# VoltageSensing.net
KiCad netlist of a schematic drawn in Altium Designer
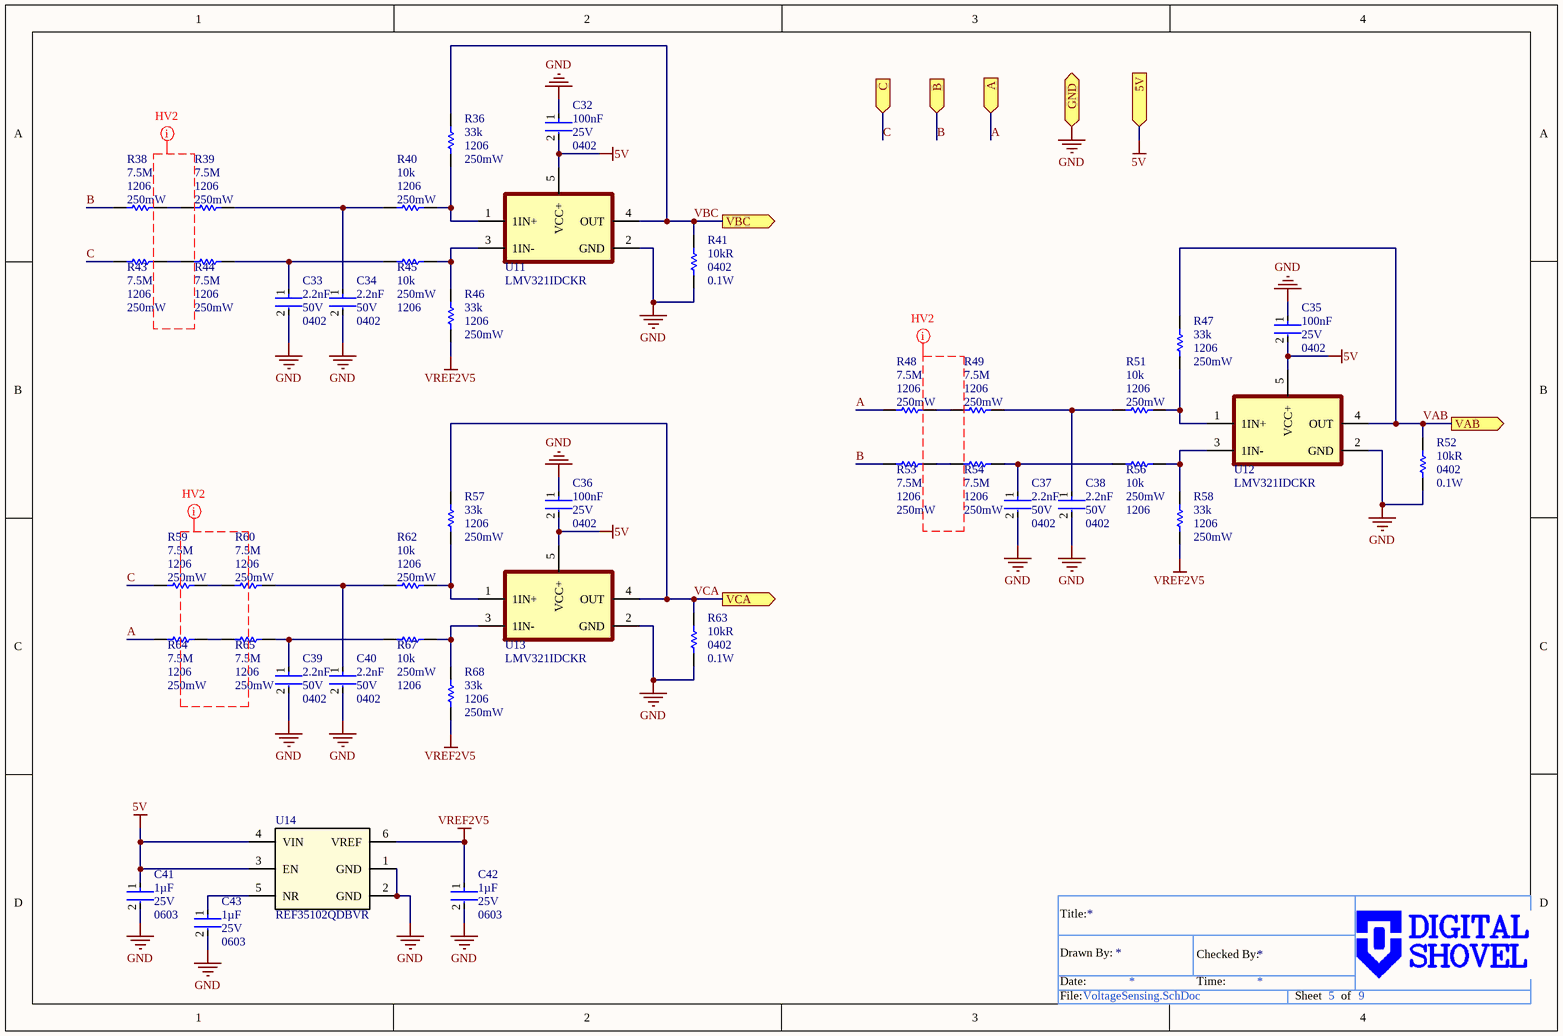
[diagram p0: VoltageSensing.SchDoc]

(export (version "E")
  (design (tool "Eeschema 10.0.6"))
  (components
    (comp (ref "C32")
      (value "100nF")
      (footprint "FP-CL830-IPC_A")
      (fields
        (field (name "VOLTAGE RATING") "25V")
        (field (name "CASE/PACKAGE") "0402")
        (field (name "Comment") "CL05B104KA5NNNC")
      )
      (libsource (lib "Digital Shovel") (part "b4654b650e69147ec39a6b967a45e02"))
    )
    (comp (ref "C33")
      (value "2.2nF")
      (footprint "FP-C0402-BB-IPC_A")
      (fields
        (field (name "VOLTAGE RATING") "50V")
        (field (name "CASE/PACKAGE") "0402")
        (field (name "Comment") "C0402C222J5RACTU")
      )
      (libsource (lib "Digital Shovel") (part "b4654b650e69147ec39a6b967a45e02"))
    )
    (comp (ref "C34")
      (value "2.2nF")
      (footprint "FP-C0402-BB-IPC_A")
      (fields
        (field (name "VOLTAGE RATING") "50V")
        (field (name "CASE/PACKAGE") "0402")
        (field (name "Comment") "C0402C222J5RACTU")
      )
      (libsource (lib "Digital Shovel") (part "b4654b650e69147ec39a6b967a45e02"))
    )
    (comp (ref "C35")
      (value "100nF")
      (footprint "FP-CL830-IPC_A")
      (fields
        (field (name "VOLTAGE RATING") "25V")
        (field (name "CASE/PACKAGE") "0402")
        (field (name "Comment") "CL05B104KA5NNNC")
      )
      (libsource (lib "Digital Shovel") (part "b4654b650e69147ec39a6b967a45e02"))
    )
    (comp (ref "C36")
      (value "100nF")
      (footprint "FP-CL830-IPC_A")
      (fields
        (field (name "VOLTAGE RATING") "25V")
        (field (name "CASE/PACKAGE") "0402")
        (field (name "Comment") "CL05B104KA5NNNC")
      )
      (libsource (lib "Digital Shovel") (part "b4654b650e69147ec39a6b967a45e02"))
    )
    (comp (ref "C37")
      (value "2.2nF")
      (footprint "FP-C0402-BB-IPC_A")
      (fields
        (field (name "VOLTAGE RATING") "50V")
        (field (name "CASE/PACKAGE") "0402")
        (field (name "Comment") "C0402C222J5RACTU")
      )
      (libsource (lib "Digital Shovel") (part "b4654b650e69147ec39a6b967a45e02"))
    )
    (comp (ref "C38")
      (value "2.2nF")
      (footprint "FP-C0402-BB-IPC_A")
      (fields
        (field (name "VOLTAGE RATING") "50V")
        (field (name "CASE/PACKAGE") "0402")
        (field (name "Comment") "C0402C222J5RACTU")
      )
      (libsource (lib "Digital Shovel") (part "b4654b650e69147ec39a6b967a45e02"))
    )
    (comp (ref "C39")
      (value "2.2nF")
      (footprint "FP-C0402-BB-IPC_A")
      (fields
        (field (name "VOLTAGE RATING") "50V")
        (field (name "CASE/PACKAGE") "0402")
        (field (name "Comment") "C0402C222J5RACTU")
      )
      (libsource (lib "Digital Shovel") (part "b4654b650e69147ec39a6b967a45e02"))
    )
    (comp (ref "C40")
      (value "2.2nF")
      (footprint "FP-C0402-BB-IPC_A")
      (fields
        (field (name "VOLTAGE RATING") "50V")
        (field (name "CASE/PACKAGE") "0402")
        (field (name "Comment") "C0402C222J5RACTU")
      )
      (libsource (lib "Digital Shovel") (part "b4654b650e69147ec39a6b967a45e02"))
    )
    (comp (ref "C41")
      (value "1µF")
      (footprint "FP-0603-L_1_6_0_1-W_0_8_0-IPC_A")
      (fields
        (field (name "VOLTAGE RATING") "25V")
        (field (name "CASE/PACKAGE") "0603")
        (field (name "Comment") "TMK107B7105KA-T")
      )
      (libsource (lib "Digital Shovel") (part "02cd4be3c70576c341d710602a673aa"))
    )
    (comp (ref "C42")
      (value "1µF")
      (footprint "FP-0603-L_1_6_0_1-W_0_8_0-IPC_A")
      (fields
        (field (name "VOLTAGE RATING") "25V")
        (field (name "CASE/PACKAGE") "0603")
        (field (name "Comment") "TMK107B7105KA-T")
      )
      (libsource (lib "Digital Shovel") (part "02cd4be3c70576c341d710602a673aa"))
    )
    (comp (ref "C43")
      (value "1µF")
      (footprint "FP-0603-L_1_6_0_1-W_0_8_0-IPC_A")
      (fields
        (field (name "VOLTAGE RATING") "25V")
        (field (name "CASE/PACKAGE") "0603")
        (field (name "Comment") "TMK107B7105KA-T")
      )
      (libsource (lib "Digital Shovel") (part "02cd4be3c70576c341d710602a673aa"))
    )
    (comp (ref "R36")
      (value "33k")
      (footprint "RESC3216X70X40NL20T20")
      (fields
        (field (name "POWER") "250mW")
        (field (name "TOLERANCE") "1%")
        (field (name "CASE/PACKAGE") "1206")
        (field (name "Comment") "RK73H2BTTD3302F")
      )
      (libsource (lib "Digital Shovel") (part "RES"))
    )
    (comp (ref "R38")
      (value "7.5M")
      (footprint "FP-KTR18-IPC_A")
      (description "Fixed Resistor, 0.25W, 7500000ohm, 500V, 1% +/-Tol, 100ppm/Cel, Surface Mount, 1206")
      (fields
        (field (name "CASE/PACKAGE") "1206")
        (field (name "POWER") "250mW")
        (field (name "TOLERANCE") "1%")
        (field (name "Comment") "KTR18EZPF7504")
      )
      (libsource (lib "Digital Shovel") (part "RES"))
    )
    (comp (ref "R39")
      (value "7.5M")
      (footprint "FP-KTR18-IPC_A")
      (description "Fixed Resistor, 0.25W, 7500000ohm, 500V, 1% +/-Tol, 100ppm/Cel, Surface Mount, 1206")
      (fields
        (field (name "CASE/PACKAGE") "1206")
        (field (name "POWER") "250mW")
        (field (name "TOLERANCE") "1%")
        (field (name "Comment") "KTR18EZPF7504")
      )
      (libsource (lib "Digital Shovel") (part "RES"))
    )
    (comp (ref "R40")
      (value "10k")
      (footprint "RESC3216X70X40NL20T20")
      (fields
        (field (name "POWER") "250mW")
        (field (name "CASE/PACKAGE") "1206")
        (field (name "TOLERANCE") "1%")
        (field (name "Comment") "RK73H2BTTD1002F")
      )
      (libsource (lib "Digital Shovel") (part "RES"))
    )
    (comp (ref "R41")
      (value "10kR")
      (footprint "RESC1005X40X25LL10T10")
      (fields
        (field (name "PACKAGE") "0402")
        (field (name "POWER") "0.1W")
        (field (name "Comment") "RK73H1ETTP1002F")
      )
      (libsource (lib "Digital Shovel") (part "RES"))
    )
    (comp (ref "R43")
      (value "7.5M")
      (footprint "FP-KTR18-IPC_A")
      (description "Fixed Resistor, 0.25W, 7500000ohm, 500V, 1% +/-Tol, 100ppm/Cel, Surface Mount, 1206")
      (fields
        (field (name "CASE/PACKAGE") "1206")
        (field (name "POWER") "250mW")
        (field (name "TOLERANCE") "1%")
        (field (name "Comment") "KTR18EZPF7504")
      )
      (libsource (lib "Digital Shovel") (part "RES"))
    )
    (comp (ref "R44")
      (value "7.5M")
      (footprint "FP-KTR18-IPC_A")
      (description "Fixed Resistor, 0.25W, 7500000ohm, 500V, 1% +/-Tol, 100ppm/Cel, Surface Mount, 1206")
      (fields
        (field (name "CASE/PACKAGE") "1206")
        (field (name "POWER") "250mW")
        (field (name "TOLERANCE") "1%")
        (field (name "Comment") "KTR18EZPF7504")
      )
      (libsource (lib "Digital Shovel") (part "RES"))
    )
    (comp (ref "R45")
      (value "10k")
      (footprint "RESC3216X70X40NL20T20")
      (fields
        (field (name "POWER") "250mW")
        (field (name "CASE/PACKAGE") "1206")
        (field (name "TOLERANCE") "1%")
        (field (name "Comment") "RK73H2BTTD1002F")
      )
      (libsource (lib "Digital Shovel") (part "RES"))
    )
    (comp (ref "R46")
      (value "33k")
      (footprint "RESC3216X70X40NL20T20")
      (fields
        (field (name "POWER") "250mW")
        (field (name "TOLERANCE") "1%")
        (field (name "CASE/PACKAGE") "1206")
        (field (name "Comment") "RK73H2BTTD3302F")
      )
      (libsource (lib "Digital Shovel") (part "RES"))
    )
    (comp (ref "R47")
      (value "33k")
      (footprint "RESC3216X70X40NL20T20")
      (fields
        (field (name "POWER") "250mW")
        (field (name "TOLERANCE") "1%")
        (field (name "CASE/PACKAGE") "1206")
        (field (name "Comment") "RK73H2BTTD3302F")
      )
      (libsource (lib "Digital Shovel") (part "RES"))
    )
    (comp (ref "R48")
      (value "7.5M")
      (footprint "FP-KTR18-IPC_A")
      (description "Fixed Resistor, 0.25W, 7500000ohm, 500V, 1% +/-Tol, 100ppm/Cel, Surface Mount, 1206")
      (fields
        (field (name "CASE/PACKAGE") "1206")
        (field (name "POWER") "250mW")
        (field (name "TOLERANCE") "1%")
        (field (name "Comment") "KTR18EZPF7504")
      )
      (libsource (lib "Digital Shovel") (part "RES"))
    )
    (comp (ref "R49")
      (value "7.5M")
      (footprint "FP-KTR18-IPC_A")
      (description "Fixed Resistor, 0.25W, 7500000ohm, 500V, 1% +/-Tol, 100ppm/Cel, Surface Mount, 1206")
      (fields
        (field (name "CASE/PACKAGE") "1206")
        (field (name "POWER") "250mW")
        (field (name "TOLERANCE") "1%")
        (field (name "Comment") "KTR18EZPF7504")
      )
      (libsource (lib "Digital Shovel") (part "RES"))
    )
    (comp (ref "R51")
      (value "10k")
      (footprint "RESC3216X70X40NL20T20")
      (fields
        (field (name "POWER") "250mW")
        (field (name "CASE/PACKAGE") "1206")
        (field (name "TOLERANCE") "1%")
        (field (name "Comment") "RK73H2BTTD1002F")
      )
      (libsource (lib "Digital Shovel") (part "RES"))
    )
    (comp (ref "R52")
      (value "10kR")
      (footprint "RESC1005X40X25LL10T10")
      (fields
        (field (name "PACKAGE") "0402")
        (field (name "POWER") "0.1W")
        (field (name "Comment") "RK73H1ETTP1002F")
      )
      (libsource (lib "Digital Shovel") (part "RES"))
    )
    (comp (ref "R53")
      (value "7.5M")
      (footprint "FP-KTR18-IPC_A")
      (description "Fixed Resistor, 0.25W, 7500000ohm, 500V, 1% +/-Tol, 100ppm/Cel, Surface Mount, 1206")
      (fields
        (field (name "CASE/PACKAGE") "1206")
        (field (name "POWER") "250mW")
        (field (name "TOLERANCE") "1%")
        (field (name "Comment") "KTR18EZPF7504")
      )
      (libsource (lib "Digital Shovel") (part "RES"))
    )
    (comp (ref "R54")
      (value "7.5M")
      (footprint "FP-KTR18-IPC_A")
      (description "Fixed Resistor, 0.25W, 7500000ohm, 500V, 1% +/-Tol, 100ppm/Cel, Surface Mount, 1206")
      (fields
        (field (name "CASE/PACKAGE") "1206")
        (field (name "POWER") "250mW")
        (field (name "TOLERANCE") "1%")
        (field (name "Comment") "KTR18EZPF7504")
      )
      (libsource (lib "Digital Shovel") (part "RES"))
    )
    (comp (ref "R56")
      (value "10k")
      (footprint "RESC3216X70X40NL20T20")
      (fields
        (field (name "POWER") "250mW")
        (field (name "CASE/PACKAGE") "1206")
        (field (name "TOLERANCE") "1%")
        (field (name "Comment") "RK73H2BTTD1002F")
      )
      (libsource (lib "Digital Shovel") (part "RES"))
    )
    (comp (ref "R57")
      (value "33k")
      (footprint "RESC3216X70X40NL20T20")
      (fields
        (field (name "POWER") "250mW")
        (field (name "TOLERANCE") "1%")
        (field (name "CASE/PACKAGE") "1206")
        (field (name "Comment") "RK73H2BTTD3302F")
      )
      (libsource (lib "Digital Shovel") (part "RES"))
    )
    (comp (ref "R58")
      (value "33k")
      (footprint "RESC3216X70X40NL20T20")
      (fields
        (field (name "POWER") "250mW")
        (field (name "TOLERANCE") "1%")
        (field (name "CASE/PACKAGE") "1206")
        (field (name "Comment") "RK73H2BTTD3302F")
      )
      (libsource (lib "Digital Shovel") (part "RES"))
    )
    (comp (ref "R59")
      (value "7.5M")
      (footprint "FP-KTR18-IPC_A")
      (description "Fixed Resistor, 0.25W, 7500000ohm, 500V, 1% +/-Tol, 100ppm/Cel, Surface Mount, 1206")
      (fields
        (field (name "CASE/PACKAGE") "1206")
        (field (name "POWER") "250mW")
        (field (name "TOLERANCE") "1%")
        (field (name "Comment") "KTR18EZPF7504")
      )
      (libsource (lib "Digital Shovel") (part "RES"))
    )
    (comp (ref "R60")
      (value "7.5M")
      (footprint "FP-KTR18-IPC_A")
      (description "Fixed Resistor, 0.25W, 7500000ohm, 500V, 1% +/-Tol, 100ppm/Cel, Surface Mount, 1206")
      (fields
        (field (name "CASE/PACKAGE") "1206")
        (field (name "POWER") "250mW")
        (field (name "TOLERANCE") "1%")
        (field (name "Comment") "KTR18EZPF7504")
      )
      (libsource (lib "Digital Shovel") (part "RES"))
    )
    (comp (ref "R62")
      (value "10k")
      (footprint "RESC3216X70X40NL20T20")
      (fields
        (field (name "POWER") "250mW")
        (field (name "CASE/PACKAGE") "1206")
        (field (name "TOLERANCE") "1%")
        (field (name "Comment") "RK73H2BTTD1002F")
      )
      (libsource (lib "Digital Shovel") (part "RES"))
    )
    (comp (ref "R63")
      (value "10kR")
      (footprint "RESC1005X40X25LL10T10")
      (fields
        (field (name "PACKAGE") "0402")
        (field (name "POWER") "0.1W")
        (field (name "Comment") "RK73H1ETTP1002F")
      )
      (libsource (lib "Digital Shovel") (part "RES"))
    )
    (comp (ref "R64")
      (value "7.5M")
      (footprint "FP-KTR18-IPC_A")
      (description "Fixed Resistor, 0.25W, 7500000ohm, 500V, 1% +/-Tol, 100ppm/Cel, Surface Mount, 1206")
      (fields
        (field (name "CASE/PACKAGE") "1206")
        (field (name "POWER") "250mW")
        (field (name "TOLERANCE") "1%")
        (field (name "Comment") "KTR18EZPF7504")
      )
      (libsource (lib "Digital Shovel") (part "RES"))
    )
    (comp (ref "R65")
      (value "7.5M")
      (footprint "FP-KTR18-IPC_A")
      (description "Fixed Resistor, 0.25W, 7500000ohm, 500V, 1% +/-Tol, 100ppm/Cel, Surface Mount, 1206")
      (fields
        (field (name "CASE/PACKAGE") "1206")
        (field (name "POWER") "250mW")
        (field (name "TOLERANCE") "1%")
        (field (name "Comment") "KTR18EZPF7504")
      )
      (libsource (lib "Digital Shovel") (part "RES"))
    )
    (comp (ref "R67")
      (value "10k")
      (footprint "RESC3216X70X40NL20T20")
      (fields
        (field (name "POWER") "250mW")
        (field (name "CASE/PACKAGE") "1206")
        (field (name "TOLERANCE") "1%")
        (field (name "Comment") "RK73H2BTTD1002F")
      )
      (libsource (lib "Digital Shovel") (part "RES"))
    )
    (comp (ref "R68")
      (value "33k")
      (footprint "RESC3216X70X40NL20T20")
      (fields
        (field (name "POWER") "250mW")
        (field (name "TOLERANCE") "1%")
        (field (name "CASE/PACKAGE") "1206")
        (field (name "Comment") "RK73H2BTTD3302F")
      )
      (libsource (lib "Digital Shovel") (part "RES"))
    )
    (comp (ref "U11")
      (value "LMV321IDCKR")
      (footprint "LMV321IDCKR-Footprint-1")
      (description "Operational Amplifier, 1 Func, 7000uV Offset-Max, BIPolar, PDSO5")
      (libsource (lib "Digital Shovel") (part "TLV9104QPWRQ1"))
    )
    (comp (ref "U12")
      (value "LMV321IDCKR")
      (footprint "LMV321IDCKR-Footprint-1")
      (description "Operational Amplifier, 1 Func, 7000uV Offset-Max, BIPolar, PDSO5")
      (libsource (lib "Digital Shovel") (part "TLV9104QPWRQ1"))
    )
    (comp (ref "U13")
      (value "LMV321IDCKR")
      (footprint "LMV321IDCKR-Footprint-1")
      (description "Operational Amplifier, 1 Func, 7000uV Offset-Max, BIPolar, PDSO5")
      (libsource (lib "Digital Shovel") (part "TLV9104QPWRQ1"))
    )
    (comp (ref "U14")
      (value "REF35102QDBVR")
      (footprint "REF35102QDBVR-Footprint-1")
      (libsource (lib "Digital Shovel") (part "REF35102QDBVR"))
    )
  )
  (nets
    (net (code "1") (name "/A") (class "Default")
      (node (ref "R48") (pin "2") (pinfunction "2_2") (pintype "passive"))
      (node (ref "R64") (pin "2") (pinfunction "2_2") (pintype "passive"))
    )
    (net (code "2") (name "/B") (class "Default")
      (node (ref "R38") (pin "2") (pinfunction "2_2") (pintype "passive"))
      (node (ref "R53") (pin "2") (pinfunction "2_2") (pintype "passive"))
    )
    (net (code "3") (name "/C") (class "Default")
      (node (ref "R43") (pin "2") (pinfunction "2_2") (pintype "passive"))
      (node (ref "R59") (pin "2") (pinfunction "2_2") (pintype "passive"))
    )
    (net (code "4") (name "/VAB") (class "Default")
      (node (ref "R47") (pin "2") (pinfunction "2_2") (pintype "passive"))
      (node (ref "R52") (pin "1") (pinfunction "1_1") (pintype "passive"))
      (node (ref "U12") (pin "4") (pinfunction "OUT_4") (pintype "passive"))
    )
    (net (code "5") (name "/VBC") (class "Default")
      (node (ref "R36") (pin "2") (pinfunction "2_2") (pintype "passive"))
      (node (ref "R41") (pin "1") (pinfunction "1_1") (pintype "passive"))
      (node (ref "U11") (pin "4") (pinfunction "OUT_4") (pintype "passive"))
    )
    (net (code "6") (name "/VCA") (class "Default")
      (node (ref "R57") (pin "2") (pinfunction "2_2") (pintype "passive"))
      (node (ref "R63") (pin "1") (pinfunction "1_1") (pintype "passive"))
      (node (ref "U13") (pin "4") (pinfunction "OUT_4") (pintype "passive"))
    )
    (net (code "7") (name "5V") (class "Default")
      (node (ref "C32") (pin "2") (pinfunction "2_2") (pintype "passive"))
      (node (ref "C35") (pin "2") (pinfunction "2_2") (pintype "passive"))
      (node (ref "C36") (pin "2") (pinfunction "2_2") (pintype "passive"))
      (node (ref "C41") (pin "1") (pinfunction "1_1") (pintype "passive"))
      (node (ref "U11") (pin "5") (pinfunction "VCC+_5") (pintype "passive"))
      (node (ref "U12") (pin "5") (pinfunction "VCC+_5") (pintype "passive"))
      (node (ref "U13") (pin "5") (pinfunction "VCC+_5") (pintype "passive"))
      (node (ref "U14") (pin "3") (pinfunction "EN_3") (pintype "passive"))
      (node (ref "U14") (pin "4") (pinfunction "VIN_4") (pintype "passive"))
    )
    (net (code "8") (name "GND") (class "Default")
      (node (ref "C32") (pin "1") (pinfunction "1_1") (pintype "passive"))
      (node (ref "C33") (pin "2") (pinfunction "2_2") (pintype "passive"))
      (node (ref "C34") (pin "2") (pinfunction "2_2") (pintype "passive"))
      (node (ref "C35") (pin "1") (pinfunction "1_1") (pintype "passive"))
      (node (ref "C36") (pin "1") (pinfunction "1_1") (pintype "passive"))
      (node (ref "C37") (pin "2") (pinfunction "2_2") (pintype "passive"))
      (node (ref "C38") (pin "2") (pinfunction "2_2") (pintype "passive"))
      (node (ref "C39") (pin "2") (pinfunction "2_2") (pintype "passive"))
      (node (ref "C40") (pin "2") (pinfunction "2_2") (pintype "passive"))
      (node (ref "C41") (pin "2") (pinfunction "2_2") (pintype "passive"))
      (node (ref "C42") (pin "2") (pinfunction "2_2") (pintype "passive"))
      (node (ref "C43") (pin "2") (pinfunction "2_2") (pintype "passive"))
      (node (ref "R41") (pin "2") (pinfunction "2_2") (pintype "passive"))
      (node (ref "R52") (pin "2") (pinfunction "2_2") (pintype "passive"))
      (node (ref "R63") (pin "2") (pinfunction "2_2") (pintype "passive"))
      (node (ref "U11") (pin "2") (pinfunction "GND_2") (pintype "passive"))
      (node (ref "U12") (pin "2") (pinfunction "GND_2") (pintype "passive"))
      (node (ref "U13") (pin "2") (pinfunction "GND_2") (pintype "passive"))
      (node (ref "U14") (pin "1") (pinfunction "GND_1") (pintype "passive"))
      (node (ref "U14") (pin "2") (pinfunction "GND_2") (pintype "passive"))
    )
    (net (code "9") (name "Net-(C33-Pad1)") (class "Default")
      (node (ref "C33") (pin "1") (pinfunction "1_1") (pintype "passive"))
      (node (ref "R44") (pin "1") (pinfunction "1_1") (pintype "passive"))
      (node (ref "R45") (pin "1") (pinfunction "1_1") (pintype "passive"))
    )
    (net (code "10") (name "Net-(C34-Pad1)") (class "Default")
      (node (ref "C34") (pin "1") (pinfunction "1_1") (pintype "passive"))
      (node (ref "R39") (pin "1") (pinfunction "1_1") (pintype "passive"))
      (node (ref "R40") (pin "1") (pinfunction "1_1") (pintype "passive"))
    )
    (net (code "11") (name "Net-(C37-Pad1)") (class "Default")
      (node (ref "C37") (pin "1") (pinfunction "1_1") (pintype "passive"))
      (node (ref "R54") (pin "1") (pinfunction "1_1") (pintype "passive"))
      (node (ref "R56") (pin "1") (pinfunction "1_1") (pintype "passive"))
    )
    (net (code "12") (name "Net-(C38-Pad1)") (class "Default")
      (node (ref "C38") (pin "1") (pinfunction "1_1") (pintype "passive"))
      (node (ref "R49") (pin "1") (pinfunction "1_1") (pintype "passive"))
      (node (ref "R51") (pin "1") (pinfunction "1_1") (pintype "passive"))
    )
    (net (code "13") (name "Net-(C39-Pad1)") (class "Default")
      (node (ref "C39") (pin "1") (pinfunction "1_1") (pintype "passive"))
      (node (ref "R65") (pin "1") (pinfunction "1_1") (pintype "passive"))
      (node (ref "R67") (pin "1") (pinfunction "1_1") (pintype "passive"))
    )
    (net (code "14") (name "Net-(C40-Pad1)") (class "Default")
      (node (ref "C40") (pin "1") (pinfunction "1_1") (pintype "passive"))
      (node (ref "R60") (pin "1") (pinfunction "1_1") (pintype "passive"))
      (node (ref "R62") (pin "1") (pinfunction "1_1") (pintype "passive"))
    )
    (net (code "15") (name "Net-(R38-Pad1)") (class "Default")
      (node (ref "R38") (pin "1") (pinfunction "1_1") (pintype "passive"))
      (node (ref "R39") (pin "2") (pinfunction "2_2") (pintype "passive"))
    )
    (net (code "16") (name "Net-(R43-Pad1)") (class "Default")
      (node (ref "R43") (pin "1") (pinfunction "1_1") (pintype "passive"))
      (node (ref "R44") (pin "2") (pinfunction "2_2") (pintype "passive"))
    )
    (net (code "17") (name "Net-(R48-Pad1)") (class "Default")
      (node (ref "R48") (pin "1") (pinfunction "1_1") (pintype "passive"))
      (node (ref "R49") (pin "2") (pinfunction "2_2") (pintype "passive"))
    )
    (net (code "18") (name "Net-(R53-Pad1)") (class "Default")
      (node (ref "R53") (pin "1") (pinfunction "1_1") (pintype "passive"))
      (node (ref "R54") (pin "2") (pinfunction "2_2") (pintype "passive"))
    )
    (net (code "19") (name "Net-(R59-Pad1)") (class "Default")
      (node (ref "R59") (pin "1") (pinfunction "1_1") (pintype "passive"))
      (node (ref "R60") (pin "2") (pinfunction "2_2") (pintype "passive"))
    )
    (net (code "20") (name "Net-(R64-Pad1)") (class "Default")
      (node (ref "R64") (pin "1") (pinfunction "1_1") (pintype "passive"))
      (node (ref "R65") (pin "2") (pinfunction "2_2") (pintype "passive"))
    )
    (net (code "21") (name "Net-(U11-1IN+)") (class "Default")
      (node (ref "R36") (pin "1") (pinfunction "1_1") (pintype "passive"))
      (node (ref "R40") (pin "2") (pinfunction "2_2") (pintype "passive"))
      (node (ref "U11") (pin "1") (pinfunction "1IN+_1") (pintype "passive"))
    )
    (net (code "22") (name "Net-(U11-1IN-)") (class "Default")
      (node (ref "R45") (pin "2") (pinfunction "2_2") (pintype "passive"))
      (node (ref "R46") (pin "2") (pinfunction "2_2") (pintype "passive"))
      (node (ref "U11") (pin "3") (pinfunction "1IN-_3") (pintype "passive"))
    )
    (net (code "23") (name "Net-(U12-1IN+)") (class "Default")
      (node (ref "R47") (pin "1") (pinfunction "1_1") (pintype "passive"))
      (node (ref "R51") (pin "2") (pinfunction "2_2") (pintype "passive"))
      (node (ref "U12") (pin "1") (pinfunction "1IN+_1") (pintype "passive"))
    )
    (net (code "24") (name "Net-(U12-1IN-)") (class "Default")
      (node (ref "R56") (pin "2") (pinfunction "2_2") (pintype "passive"))
      (node (ref "R58") (pin "2") (pinfunction "2_2") (pintype "passive"))
      (node (ref "U12") (pin "3") (pinfunction "1IN-_3") (pintype "passive"))
    )
    (net (code "25") (name "Net-(U13-1IN+)") (class "Default")
      (node (ref "R57") (pin "1") (pinfunction "1_1") (pintype "passive"))
      (node (ref "R62") (pin "2") (pinfunction "2_2") (pintype "passive"))
      (node (ref "U13") (pin "1") (pinfunction "1IN+_1") (pintype "passive"))
    )
    (net (code "26") (name "Net-(U13-1IN-)") (class "Default")
      (node (ref "R67") (pin "2") (pinfunction "2_2") (pintype "passive"))
      (node (ref "R68") (pin "2") (pinfunction "2_2") (pintype "passive"))
      (node (ref "U13") (pin "3") (pinfunction "1IN-_3") (pintype "passive"))
    )
    (net (code "27") (name "Net-(U14-NR)") (class "Default")
      (node (ref "C43") (pin "1") (pinfunction "1_1") (pintype "passive"))
      (node (ref "U14") (pin "5") (pinfunction "NR_5") (pintype "passive"))
    )
    (net (code "28") (name "VREF2V5") (class "Default")
      (node (ref "C42") (pin "1") (pinfunction "1_1") (pintype "passive"))
      (node (ref "R46") (pin "1") (pinfunction "1_1") (pintype "passive"))
      (node (ref "R58") (pin "1") (pinfunction "1_1") (pintype "passive"))
      (node (ref "R68") (pin "1") (pinfunction "1_1") (pintype "passive"))
      (node (ref "U14") (pin "6") (pinfunction "VREF_6") (pintype "passive"))
    )
  )
)
